# leto_ppm.net
KiCad netlist of a schematic drawn in EAGLE
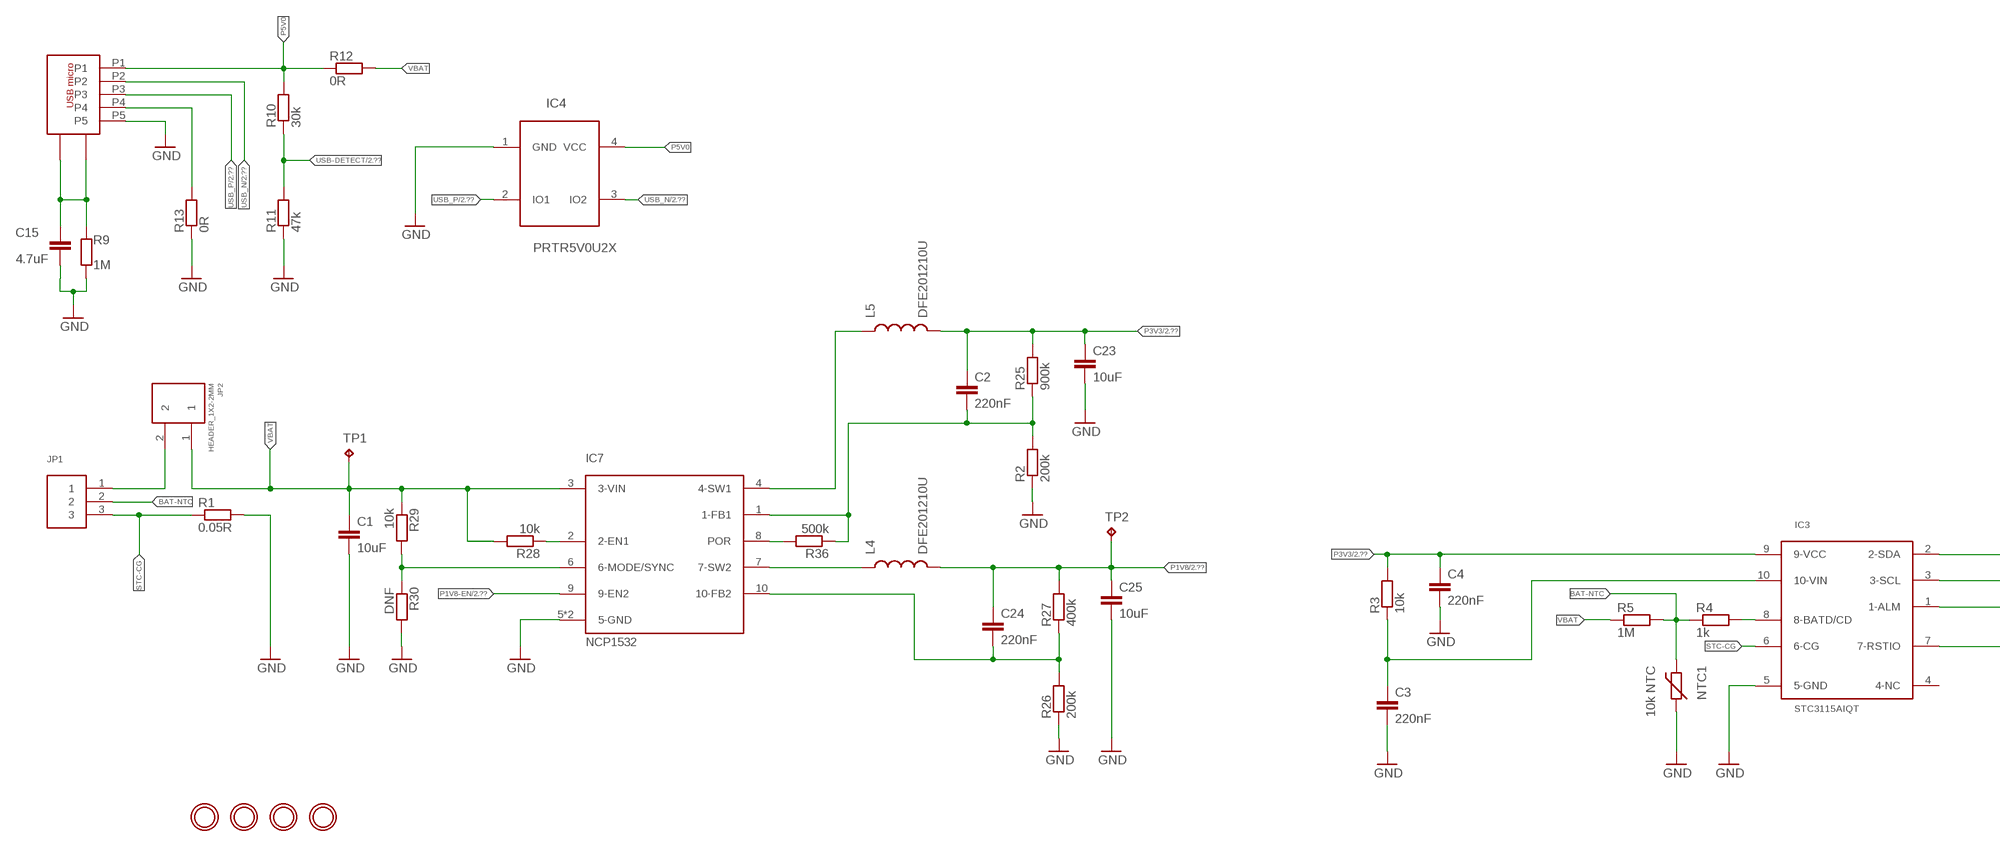
[diagram p0: schematic, sheet 1, part 1 of 2]
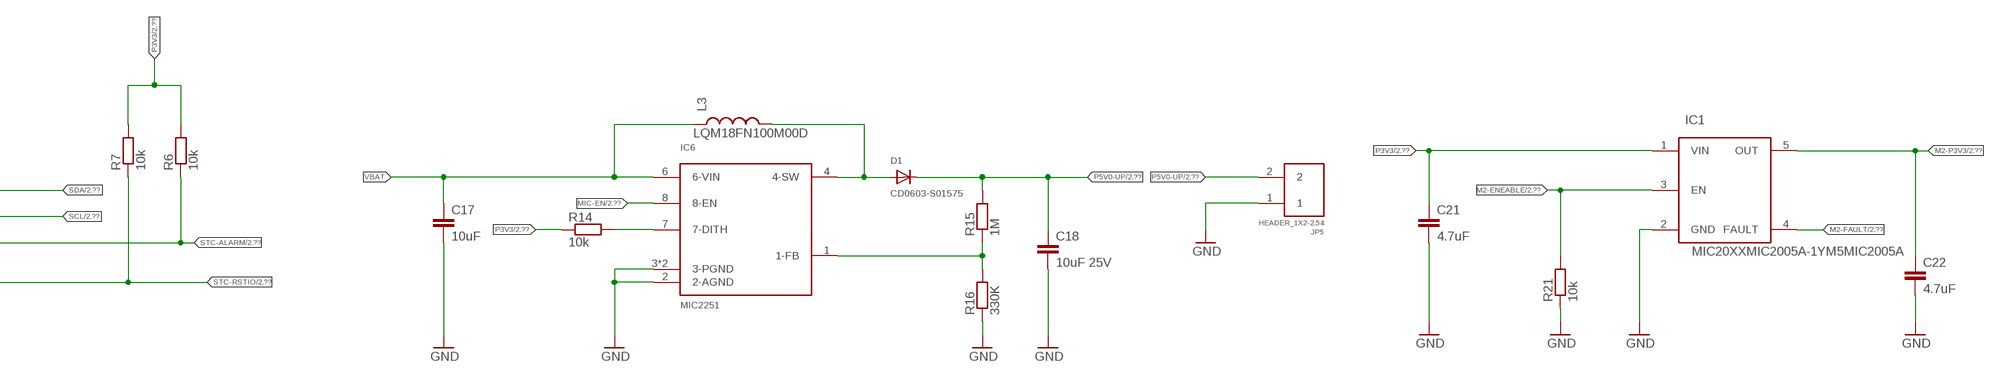
[diagram p1: schematic, sheet 1, part 2 of 2]
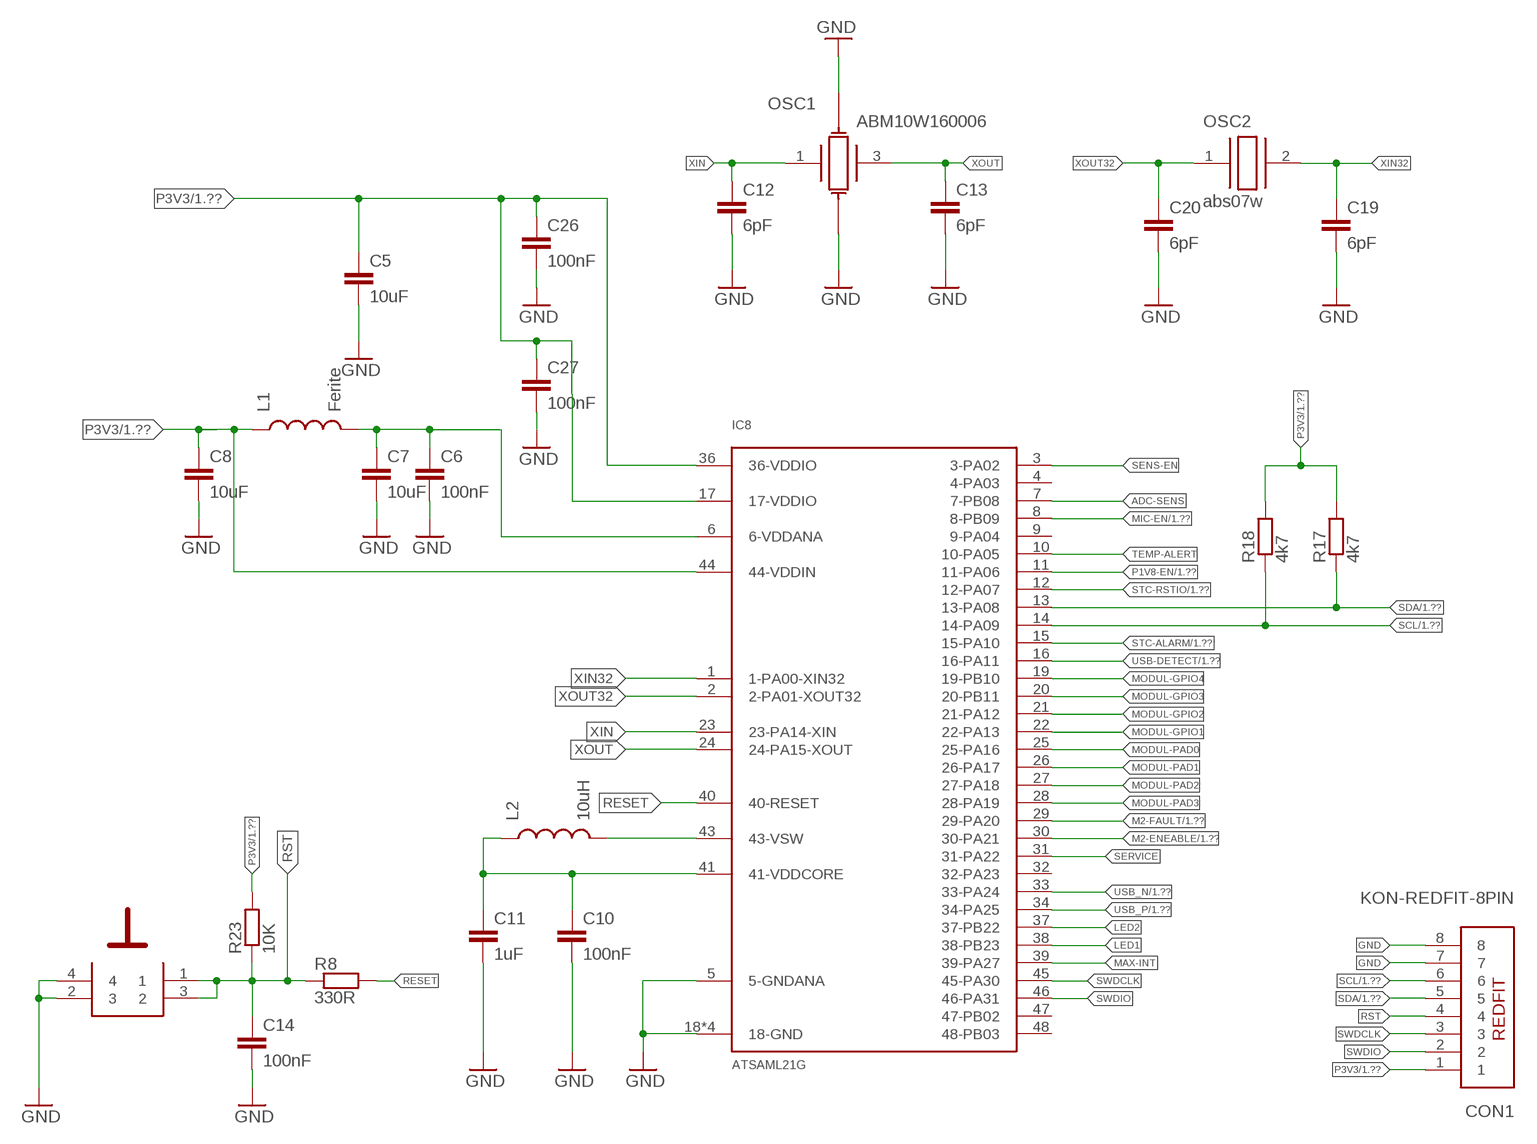
[diagram p2: schematic, sheet 2, part 1 of 2]
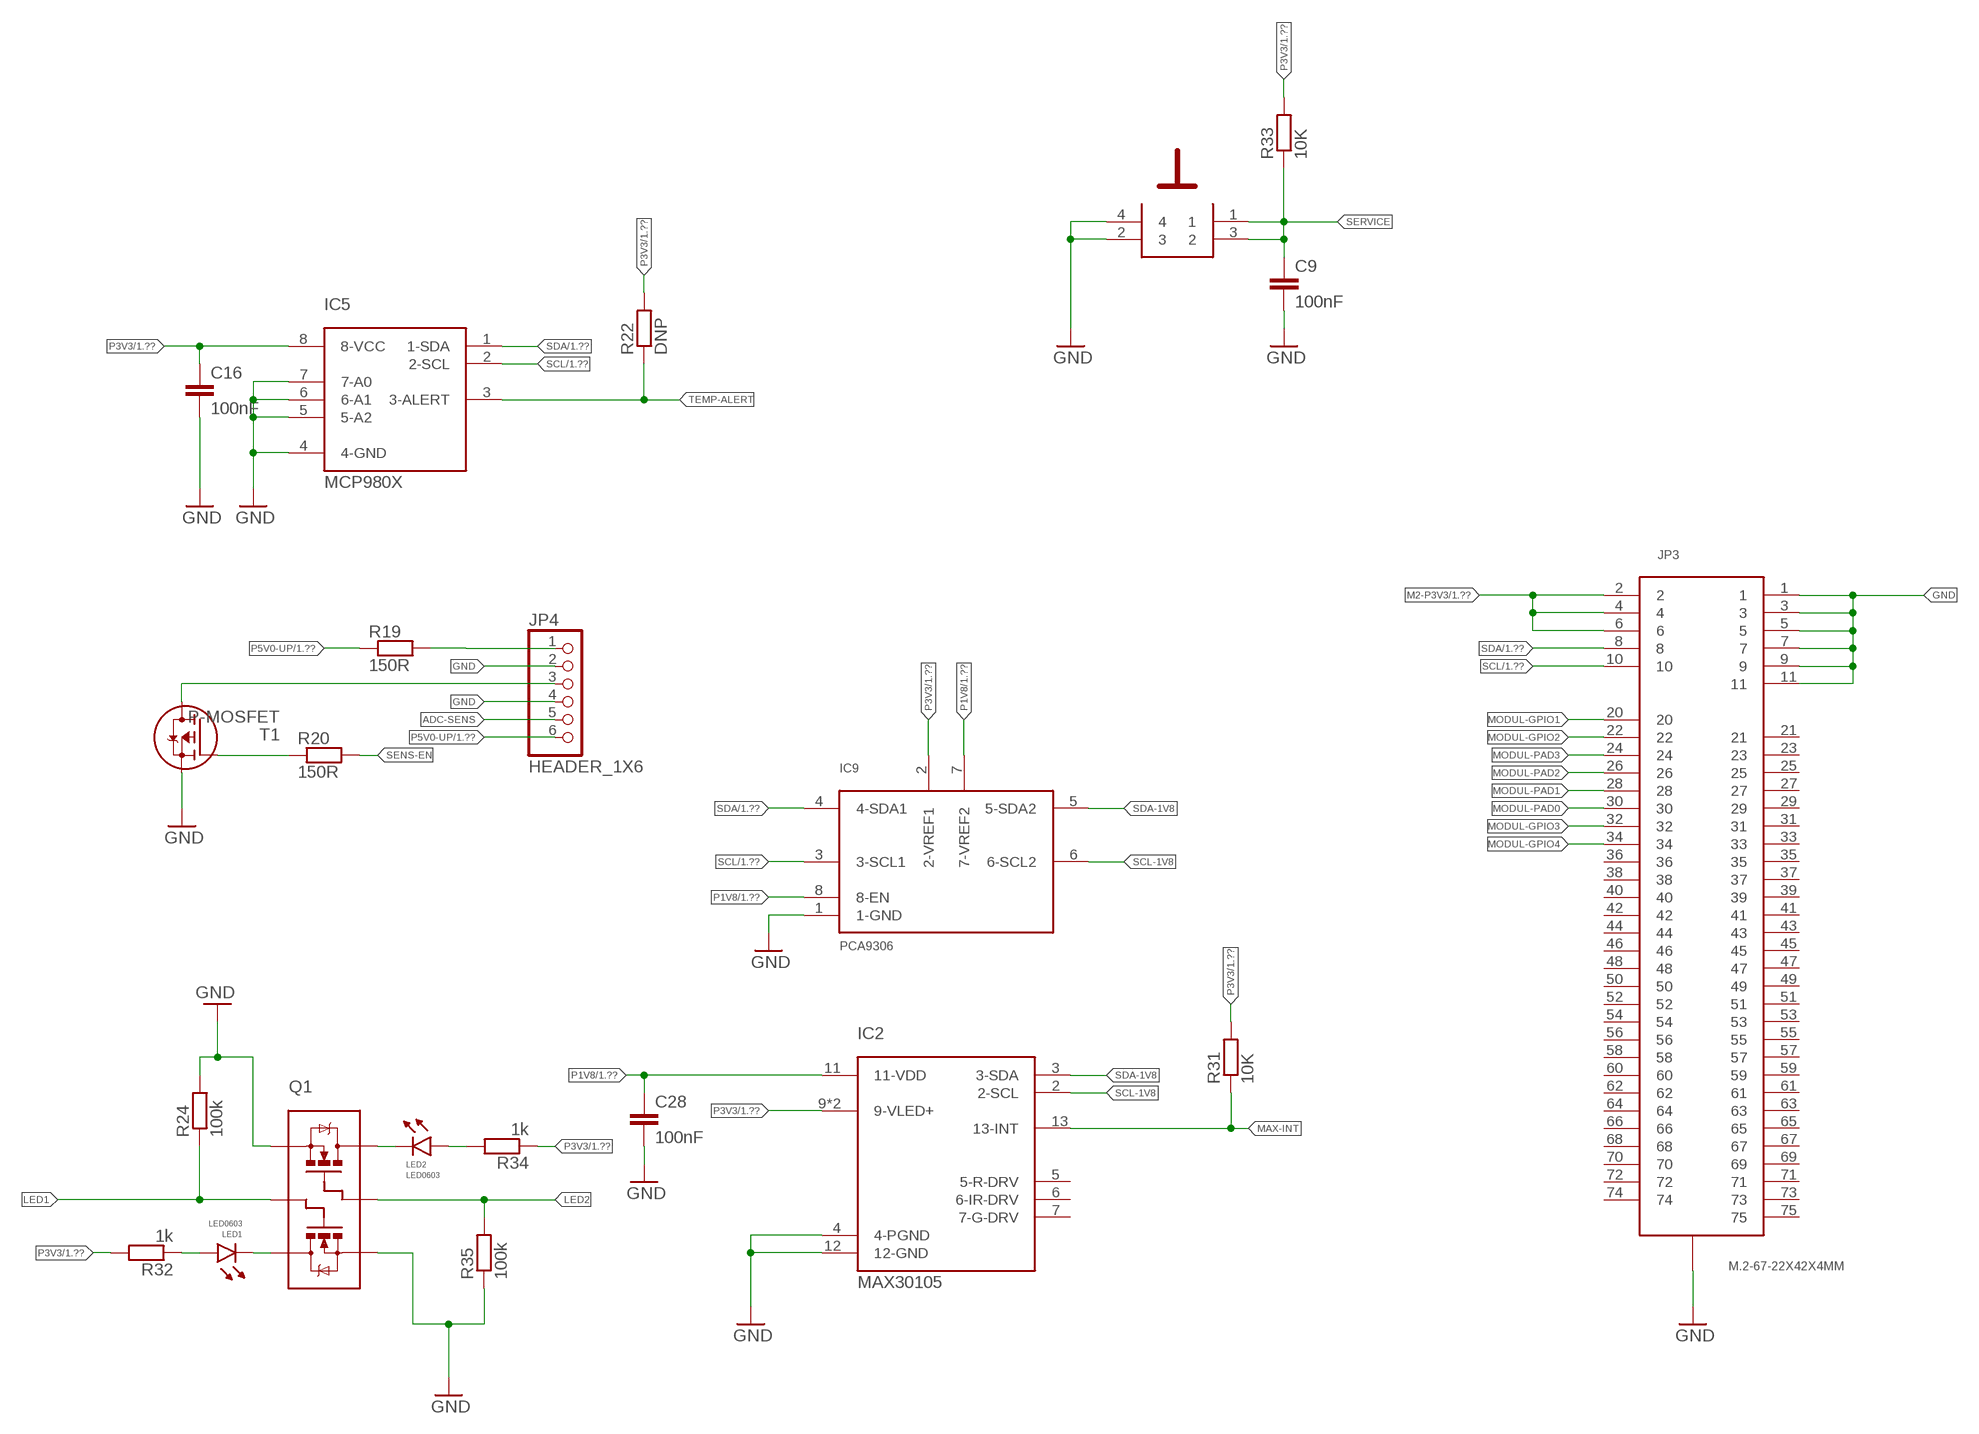
[diagram p3: schematic, sheet 2, part 2 of 2]

(export (version "E")
  (design (tool "Eeschema 10.0.6"))
  (components
    (comp (ref "C1")
      (value "10uF")
      (footprint "eagle-import:C0603")
      (libsource (lib "eagle-import") (part "C-EUC0603"))
    )
    (comp (ref "C2")
      (value "220nF")
      (footprint "eagle-import:C0402-SMALL")
      (libsource (lib "eagle-import") (part "C-EUC0402-SMALL"))
    )
    (comp (ref "C3")
      (value "220nF")
      (footprint "eagle-import:C0402-SMALL")
      (libsource (lib "eagle-import") (part "C-EUC0402-SMALL"))
    )
    (comp (ref "C4")
      (value "220nF")
      (footprint "eagle-import:C0402-SMALL")
      (libsource (lib "eagle-import") (part "C-EUC0402-SMALL"))
    )
    (comp (ref "C15")
      (value "4.7uF")
      (footprint "eagle-import:C0402-SMALL")
      (libsource (lib "eagle-import") (part "C-EUC0402-SMALL"))
    )
    (comp (ref "C17")
      (value "10uF")
      (footprint "eagle-import:C0603")
      (libsource (lib "eagle-import") (part "C-EUC0603"))
    )
    (comp (ref "C18")
      (value "10uF 25V")
      (footprint "eagle-import:C0603")
      (libsource (lib "eagle-import") (part "C-EUC0603"))
    )
    (comp (ref "C21")
      (value "4.7uF")
      (footprint "eagle-import:C0402-SMALL")
      (libsource (lib "eagle-import") (part "C-EUC0402-SMALL"))
    )
    (comp (ref "C22")
      (value "4.7uF")
      (footprint "eagle-import:C0402-SMALL")
      (libsource (lib "eagle-import") (part "C-EUC0402-SMALL"))
    )
    (comp (ref "C23")
      (value "10uF")
      (footprint "eagle-import:C0603")
      (libsource (lib "eagle-import") (part "C-EUC0603"))
    )
    (comp (ref "C24")
      (value "220nF")
      (footprint "eagle-import:C0402-SMALL")
      (libsource (lib "eagle-import") (part "C-EUC0402-SMALL"))
    )
    (comp (ref "C25")
      (value "10uF")
      (footprint "eagle-import:C0603")
      (libsource (lib "eagle-import") (part "C-EUC0603"))
    )
    (comp (ref "D1")
      (value "CD0603-S01575")
      (footprint "eagle-import:0603-DIODE")
      (libsource (lib "eagle-import") (part "DIODE"))
    )
    (comp (ref "IC1")
      (value "MIC20XXMIC2005A-1YM5MIC2005A")
      (footprint "eagle-import:SOT23-5")
      (libsource (lib "eagle-import") (part "MIC20XXMIC2005AMIC2005A-1YM5"))
    )
    (comp (ref "IC3")
      (value "STC3115AIQT")
      (footprint "eagle-import:DFN10_2X3MM")
      (libsource (lib "eagle-import") (part "STC3115AIQT"))
    )
    (comp (ref "IC4")
      (value "PRTR5V0U2X")
      (footprint "eagle-import:SOT143")
      (libsource (lib "eagle-import") (part "PRTR5V0U2X"))
    )
    (comp (ref "IC6")
      (value "MIC2251")
      (footprint "eagle-import:MLF-8-2X2")
      (libsource (lib "eagle-import") (part "MIC2251"))
    )
    (comp (ref "IC7")
      (value "NCP1532")
      (footprint "eagle-import:UDNF10-3X3")
      (libsource (lib "eagle-import") (part "NCP1532"))
    )
    (comp (ref "JP1")
      (value "HEADER_1X32.54MM")
      (footprint "eagle-import:1X3-2.54MM")
      (libsource (lib "eagle-import") (part "HEADER_1X32.54MM"))
    )
    (comp (ref "JP2")
      (value "HEADER_1X2-2MM")
      (footprint "eagle-import:1X2_2MM")
      (libsource (lib "eagle-import") (part "HEADER_1X2-2MM"))
    )
    (comp (ref "JP5")
      (value "HEADER_1X2-2.54")
      (footprint "eagle-import:1X2-2.54MM")
      (libsource (lib "eagle-import") (part "HEADER_1X2-2.54"))
    )
    (comp (ref "L3")
      (value "LQM18FN100M00D")
      (footprint "eagle-import:0603")
      (libsource (lib "eagle-import") (part "INDUCTOR0603"))
    )
    (comp (ref "L4")
      (value "DFE201210U")
      (footprint "eagle-import:0805")
      (libsource (lib "eagle-import") (part "INDUCTOR0805"))
    )
    (comp (ref "L5")
      (value "DFE201210U")
      (footprint "eagle-import:0805")
      (libsource (lib "eagle-import") (part "INDUCTOR0805"))
    )
    (comp (ref "MD1")
      (value "MOUNTINGHOLE2.5")
      (footprint "eagle-import:MOUNTINGHOLE_2.5_PLATED")
      (libsource (lib "eagle-import") (part "MOUNTINGHOLE2.5"))
    )
    (comp (ref "MD2")
      (value "MOUNTINGHOLE2.5")
      (footprint "eagle-import:MOUNTINGHOLE_2.5_PLATED")
      (libsource (lib "eagle-import") (part "MOUNTINGHOLE2.5"))
    )
    (comp (ref "MD3")
      (value "MOUNTINGHOLE2.5")
      (footprint "eagle-import:MOUNTINGHOLE_2.5_PLATED")
      (libsource (lib "eagle-import") (part "MOUNTINGHOLE2.5"))
    )
    (comp (ref "MD4")
      (value "MOUNTINGHOLE2.5")
      (footprint "eagle-import:MOUNTINGHOLE_2.5_PLATED")
      (libsource (lib "eagle-import") (part "MOUNTINGHOLE2.5"))
    )
    (comp (ref "NTC1")
      (value "10k NTC")
      (footprint "eagle-import:C0402-SMALL")
      (libsource (lib "eagle-import") (part "RESISTOR-NTC0402"))
    )
    (comp (ref "R1")
      (value "0.05R")
      (footprint "eagle-import:0603-RES")
      (libsource (lib "eagle-import") (part "RESISTOR0603-RES"))
    )
    (comp (ref "R2")
      (value "200k")
      (footprint "eagle-import:C0402-SMALL")
      (libsource (lib "eagle-import") (part "RESISTORC0402-SMALL"))
    )
    (comp (ref "R3")
      (value "10k")
      (footprint "eagle-import:C0402-SMALL")
      (libsource (lib "eagle-import") (part "RESISTORC0402-SMALL"))
    )
    (comp (ref "R4")
      (value "1k")
      (footprint "eagle-import:C0402-SMALL")
      (libsource (lib "eagle-import") (part "RESISTORC0402-SMALL"))
    )
    (comp (ref "R5")
      (value "1M")
      (footprint "eagle-import:C0402-SMALL")
      (libsource (lib "eagle-import") (part "RESISTORC0402-SMALL"))
    )
    (comp (ref "R6")
      (value "10k")
      (footprint "eagle-import:C0402-SMALL")
      (libsource (lib "eagle-import") (part "RESISTORC0402-SMALL"))
    )
    (comp (ref "R7")
      (value "10k")
      (footprint "eagle-import:C0402-SMALL")
      (libsource (lib "eagle-import") (part "RESISTORC0402-SMALL"))
    )
    (comp (ref "R9")
      (value "1M")
      (footprint "eagle-import:C0402-SMALL")
      (libsource (lib "eagle-import") (part "RESISTORC0402-SMALL"))
    )
    (comp (ref "R10")
      (value "30k")
      (footprint "eagle-import:C0402-SMALL")
      (libsource (lib "eagle-import") (part "RESISTORC0402-SMALL"))
    )
    (comp (ref "R11")
      (value "47k")
      (footprint "eagle-import:C0402-SMALL")
      (libsource (lib "eagle-import") (part "RESISTORC0402-SMALL"))
    )
    (comp (ref "R12")
      (value "0R")
      (footprint "eagle-import:C0402-SMALL")
      (libsource (lib "eagle-import") (part "RESISTORC0402-SMALL"))
    )
    (comp (ref "R13")
      (value "0R")
      (footprint "eagle-import:C0402-SMALL")
      (libsource (lib "eagle-import") (part "RESISTORC0402-SMALL"))
    )
    (comp (ref "R14")
      (value "10k")
      (footprint "eagle-import:C0402-SMALL")
      (libsource (lib "eagle-import") (part "RESISTORC0402-SMALL"))
    )
    (comp (ref "R15")
      (value "1M")
      (footprint "eagle-import:C0402-SMALL")
      (libsource (lib "eagle-import") (part "RESISTORC0402-SMALL"))
    )
    (comp (ref "R16")
      (value "330K")
      (footprint "eagle-import:C0402-SMALL")
      (libsource (lib "eagle-import") (part "RESISTORC0402-SMALL"))
    )
    (comp (ref "R21")
      (value "10k")
      (footprint "eagle-import:C0402-SMALL")
      (libsource (lib "eagle-import") (part "RESISTORC0402-SMALL"))
    )
    (comp (ref "R25")
      (value "900k")
      (footprint "eagle-import:C0402-SMALL")
      (libsource (lib "eagle-import") (part "RESISTORC0402-SMALL"))
    )
    (comp (ref "R26")
      (value "200k")
      (footprint "eagle-import:C0402-SMALL")
      (libsource (lib "eagle-import") (part "RESISTORC0402-SMALL"))
    )
    (comp (ref "R27")
      (value "400k")
      (footprint "eagle-import:C0402-SMALL")
      (libsource (lib "eagle-import") (part "RESISTORC0402-SMALL"))
    )
    (comp (ref "R28")
      (value "10k")
      (footprint "eagle-import:C0402-SMALL")
      (libsource (lib "eagle-import") (part "RESISTORC0402-SMALL"))
    )
    (comp (ref "R29")
      (value "10k")
      (footprint "eagle-import:C0402-SMALL")
      (libsource (lib "eagle-import") (part "RESISTORC0402-SMALL"))
    )
    (comp (ref "R30")
      (value "DNF")
      (footprint "eagle-import:C0402-SMALL")
      (libsource (lib "eagle-import") (part "RESISTORC0402-SMALL"))
    )
    (comp (ref "R36")
      (value "500k")
      (footprint "eagle-import:C0402-SMALL")
      (libsource (lib "eagle-import") (part "RESISTORC0402-SMALL"))
    )
    (comp (ref "TP1")
      (value "TPTP20R")
      (footprint "eagle-import:TP20R")
      (libsource (lib "eagle-import") (part "TPTP20R"))
    )
    (comp (ref "TP2")
      (value "TPTP11R")
      (footprint "eagle-import:TP11R")
      (libsource (lib "eagle-import") (part "testpad_385_TPTP11R"))
    )
    (comp (ref "USB1")
      (value "USB3140-30")
      (footprint "eagle-import:USB3140-30-0230")
      (libsource (lib "eagle-import") (part "USB3140-30"))
    )
    (comp (ref "C5")
      (value "10uF")
      (footprint "eagle-import:C0603")
      (libsource (lib "eagle-import") (part "C-EUC0603"))
    )
    (comp (ref "C6")
      (value "100nF")
      (footprint "eagle-import:C0402-SMALL")
      (libsource (lib "eagle-import") (part "C-EUC0402-SMALL"))
    )
    (comp (ref "C7")
      (value "10uF")
      (footprint "eagle-import:C0603")
      (libsource (lib "eagle-import") (part "C-EUC0603"))
    )
    (comp (ref "C8")
      (value "10uF")
      (footprint "eagle-import:C0603")
      (libsource (lib "eagle-import") (part "C-EUC0603"))
    )
    (comp (ref "C9")
      (value "100nF")
      (footprint "eagle-import:C0402-SMALL")
      (libsource (lib "eagle-import") (part "C-EUC0402-SMALL"))
    )
    (comp (ref "C10")
      (value "100nF")
      (footprint "eagle-import:C0402-SMALL")
      (libsource (lib "eagle-import") (part "C-EUC0402-SMALL"))
    )
    (comp (ref "C11")
      (value "1uF")
      (footprint "eagle-import:C0402-SMALL")
      (libsource (lib "eagle-import") (part "C-EUC0402-SMALL"))
    )
    (comp (ref "C12")
      (value "6pF")
      (footprint "eagle-import:C0402-SMALL")
      (libsource (lib "eagle-import") (part "C-EUC0402-SMALL"))
    )
    (comp (ref "C13")
      (value "6pF")
      (footprint "eagle-import:C0402-SMALL")
      (libsource (lib "eagle-import") (part "C-EUC0402-SMALL"))
    )
    (comp (ref "C14")
      (value "100nF")
      (footprint "eagle-import:C0402-SMALL")
      (libsource (lib "eagle-import") (part "C-EUC0402-SMALL"))
    )
    (comp (ref "C16")
      (value "100nF")
      (footprint "eagle-import:C0402-SMALL")
      (libsource (lib "eagle-import") (part "C-EUC0402-SMALL"))
    )
    (comp (ref "C19")
      (value "6pF")
      (footprint "eagle-import:C0402-SMALL")
      (libsource (lib "eagle-import") (part "C-EUC0402-SMALL"))
    )
    (comp (ref "C20")
      (value "6pF")
      (footprint "eagle-import:C0402-SMALL")
      (libsource (lib "eagle-import") (part "C-EUC0402-SMALL"))
    )
    (comp (ref "C26")
      (value "100nF")
      (footprint "eagle-import:C0402-SMALL")
      (libsource (lib "eagle-import") (part "C-EUC0402-SMALL"))
    )
    (comp (ref "C27")
      (value "100nF")
      (footprint "eagle-import:C0402-SMALL")
      (libsource (lib "eagle-import") (part "C-EUC0402-SMALL"))
    )
    (comp (ref "C28")
      (value "100nF")
      (footprint "eagle-import:C0402-SMALL")
      (libsource (lib "eagle-import") (part "C-EUC0402-SMALL"))
    )
    (comp (ref "CON1")
      (value "KON-REDFIT-8PIN")
      (footprint "eagle-import:KON-REDFIT-8PIN")
      (libsource (lib "eagle-import") (part "KON-REDFIT-8PIN"))
    )
    (comp (ref "IC2")
      (value "MAX30105")
      (footprint "eagle-import:14-OESIP")
      (libsource (lib "eagle-import") (part "MAX30105"))
    )
    (comp (ref "IC5")
      (value "MCP980X")
      (footprint "eagle-import:DNF82X3MM")
      (libsource (lib "eagle-import") (part "MCP980X"))
    )
    (comp (ref "IC8")
      (value "ATSAML21G")
      (footprint "eagle-import:QFN48")
      (libsource (lib "eagle-import") (part "ATSAML21G"))
    )
    (comp (ref "IC9")
      (value "PCA9306")
      (footprint "eagle-import:SO8")
      (libsource (lib "eagle-import") (part "PCA9306"))
    )
    (comp (ref "JP3")
      (value "M.2-67-22X42X4MM")
      (footprint "eagle-import:M2-67POS-0.5MM")
      (libsource (lib "eagle-import") (part "M.2-67-22X42X4MM"))
    )
    (comp (ref "JP4")
      (value "HEADER_1X6")
      (footprint "eagle-import:1X6_2.54")
      (libsource (lib "eagle-import") (part "HEADER_1X6"))
    )
    (comp (ref "L1")
      (value "Ferite")
      (footprint "eagle-import:0603")
      (libsource (lib "eagle-import") (part "INDUCTOR0603"))
    )
    (comp (ref "L2")
      (value "10uH")
      (footprint "eagle-import:0603")
      (libsource (lib "eagle-import") (part "INDUCTOR0603"))
    )
    (comp (ref "LED1")
      (value "LED0603")
      (footprint "eagle-import:0603-DIODE")
      (libsource (lib "eagle-import") (part "LED0603"))
    )
    (comp (ref "LED2")
      (value "LED0603")
      (footprint "eagle-import:0603-DIODE")
      (libsource (lib "eagle-import") (part "LED0603"))
    )
    (comp (ref "OSC1")
      (value "ABM10W160006")
      (footprint "eagle-import:ABM10W")
      (libsource (lib "eagle-import") (part "CRYSTAL-GNDABM10W"))
    )
    (comp (ref "OSC2")
      (value "abs07w")
      (footprint "eagle-import:ABS07W")
      (libsource (lib "eagle-import") (part "CRYSTAL"))
    )
    (comp (ref "Q1")
      (value "MOSFET-N-X2-SOT363")
      (footprint "eagle-import:SOT363")
      (libsource (lib "eagle-import") (part "MOSFET-N-X2-SOT363"))
    )
    (comp (ref "R8")
      (value "330R")
      (footprint "eagle-import:C0402-SMALL")
      (libsource (lib "eagle-import") (part "RESISTORC0402-SMALL"))
    )
    (comp (ref "R17")
      (value "4k7")
      (footprint "eagle-import:C0402-SMALL")
      (libsource (lib "eagle-import") (part "RESISTORC0402-SMALL"))
    )
    (comp (ref "R18")
      (value "4k7")
      (footprint "eagle-import:C0402-SMALL")
      (libsource (lib "eagle-import") (part "RESISTORC0402-SMALL"))
    )
    (comp (ref "R19")
      (value "150R")
      (footprint "eagle-import:C0402-SMALL")
      (libsource (lib "eagle-import") (part "RESISTORC0402-SMALL"))
    )
    (comp (ref "R20")
      (value "150R")
      (footprint "eagle-import:C0402-SMALL")
      (libsource (lib "eagle-import") (part "RESISTORC0402-SMALL"))
    )
    (comp (ref "R22")
      (value "DNP")
      (footprint "eagle-import:C0402-SMALL")
      (libsource (lib "eagle-import") (part "RESISTORC0402-SMALL"))
    )
    (comp (ref "R23")
      (value "10K")
      (footprint "eagle-import:C0402-SMALL")
      (libsource (lib "eagle-import") (part "RESISTORC0402-SMALL"))
    )
    (comp (ref "R24")
      (value "100k")
      (footprint "eagle-import:C0402-SMALL")
      (libsource (lib "eagle-import") (part "RESISTORC0402-SMALL"))
    )
    (comp (ref "R31")
      (value "10K")
      (footprint "eagle-import:C0402-SMALL")
      (libsource (lib "eagle-import") (part "RESISTORC0402-SMALL"))
    )
    (comp (ref "R32")
      (value "1k")
      (footprint "eagle-import:C0402-SMALL")
      (libsource (lib "eagle-import") (part "RESISTORC0402-SMALL"))
    )
    (comp (ref "R33")
      (value "10K")
      (footprint "eagle-import:C0402-SMALL")
      (libsource (lib "eagle-import") (part "RESISTORC0402-SMALL"))
    )
    (comp (ref "R34")
      (value "1k")
      (footprint "eagle-import:C0402-SMALL")
      (libsource (lib "eagle-import") (part "RESISTORC0402-SMALL"))
    )
    (comp (ref "R35")
      (value "100k")
      (footprint "eagle-import:C0402-SMALL")
      (libsource (lib "eagle-import") (part "RESISTORC0402-SMALL"))
    )
    (comp (ref "RESET")
      (value "TACTB")
      (footprint "eagle-import:TACTB-64K-F")
      (libsource (lib "eagle-import") (part "TACTB"))
    )
    (comp (ref "SERVICE")
      (value "TACTB")
      (footprint "eagle-import:TACTB-64K-F")
      (libsource (lib "eagle-import") (part "TACTB"))
    )
    (comp (ref "T1")
      (value "P-MOSFET")
      (footprint "eagle-import:SOT23-R")
      (libsource (lib "eagle-import") (part "P-MOSFET"))
    )
  )
  (nets
    (net (code "1") (name "ADC-SENS") (class "Default")
      (node (ref "IC8") (pin "7") (pinfunction "7-PB08_7") (pintype "bidirectional"))
      (node (ref "JP4") (pin "5") (pinfunction "5_5") (pintype "passive"))
    )
    (net (code "2") (name "BAT-NTC") (class "Default")
      (node (ref "JP1") (pin "2") (pinfunction "2_2") (pintype "bidirectional"))
      (node (ref "NTC1") (pin "1") (pinfunction "1_1") (pintype "passive"))
      (node (ref "R4") (pin "1") (pinfunction "1_1") (pintype "passive"))
      (node (ref "R5") (pin "2") (pinfunction "2_2") (pintype "passive"))
    )
    (net (code "3") (name "GND") (class "Default")
      (node (ref "C1") (pin "2") (pinfunction "2_2") (pintype "passive"))
      (node (ref "C10") (pin "2") (pinfunction "2_2") (pintype "passive"))
      (node (ref "C11") (pin "2") (pinfunction "2_2") (pintype "passive"))
      (node (ref "C12") (pin "2") (pinfunction "2_2") (pintype "passive"))
      (node (ref "C13") (pin "2") (pinfunction "2_2") (pintype "passive"))
      (node (ref "C14") (pin "2") (pinfunction "2_2") (pintype "passive"))
      (node (ref "C15") (pin "2") (pinfunction "2_2") (pintype "passive"))
      (node (ref "C16") (pin "2") (pinfunction "2_2") (pintype "passive"))
      (node (ref "C17") (pin "2") (pinfunction "2_2") (pintype "passive"))
      (node (ref "C18") (pin "2") (pinfunction "2_2") (pintype "passive"))
      (node (ref "C19") (pin "2") (pinfunction "2_2") (pintype "passive"))
      (node (ref "C20") (pin "2") (pinfunction "2_2") (pintype "passive"))
      (node (ref "C21") (pin "2") (pinfunction "2_2") (pintype "passive"))
      (node (ref "C22") (pin "2") (pinfunction "2_2") (pintype "passive"))
      (node (ref "C23") (pin "2") (pinfunction "2_2") (pintype "passive"))
      (node (ref "C25") (pin "2") (pinfunction "2_2") (pintype "passive"))
      (node (ref "C26") (pin "2") (pinfunction "2_2") (pintype "passive"))
      (node (ref "C27") (pin "2") (pinfunction "2_2") (pintype "passive"))
      (node (ref "C28") (pin "2") (pinfunction "2_2") (pintype "passive"))
      (node (ref "C3") (pin "2") (pinfunction "2_2") (pintype "passive"))
      (node (ref "C4") (pin "2") (pinfunction "2_2") (pintype "passive"))
      (node (ref "C5") (pin "2") (pinfunction "2_2") (pintype "passive"))
      (node (ref "C6") (pin "2") (pinfunction "2_2") (pintype "passive"))
      (node (ref "C7") (pin "2") (pinfunction "2_2") (pintype "passive"))
      (node (ref "C8") (pin "2") (pinfunction "2_2") (pintype "passive"))
      (node (ref "C9") (pin "2") (pinfunction "2_2") (pintype "passive"))
      (node (ref "CON1") (pin "7") (pinfunction "7_7") (pintype "bidirectional"))
      (node (ref "CON1") (pin "8") (pinfunction "8_8") (pintype "bidirectional"))
      (node (ref "IC1") (pin "2") (pinfunction "GND_2") (pintype "bidirectional"))
      (node (ref "IC2") (pin "12") (pinfunction "12-GND_12") (pintype "bidirectional"))
      (node (ref "IC2") (pin "4") (pinfunction "4-PGND_4") (pintype "bidirectional"))
      (node (ref "IC3") (pin "5") (pinfunction "5-GND_5") (pintype "bidirectional"))
      (node (ref "IC4") (pin "1") (pinfunction "GND_1") (pintype "bidirectional"))
      (node (ref "IC5") (pin "4") (pinfunction "4-GND_4") (pintype "bidirectional"))
      (node (ref "IC5") (pin "5") (pinfunction "5-A2_5") (pintype "bidirectional"))
      (node (ref "IC5") (pin "6") (pinfunction "6-A1_6") (pintype "bidirectional"))
      (node (ref "IC5") (pin "7") (pinfunction "7-A0_7") (pintype "bidirectional"))
      (node (ref "IC6") (pin "2") (pinfunction "2-AGND_2") (pintype "bidirectional"))
      (node (ref "IC6") (pin "3") (pinfunction "3-PGND_3") (pintype "bidirectional"))
      (node (ref "IC6") (pin "EP") (pinfunction "3-PGND_EP") (pintype "bidirectional"))
      (node (ref "IC7") (pin "5") (pinfunction "5-GND_5") (pintype "bidirectional"))
      (node (ref "IC7") (pin "P$11") (pinfunction "5-GND_P$11") (pintype "bidirectional"))
      (node (ref "IC8") (pin "18") (pinfunction "18-GND_18") (pintype "bidirectional"))
      (node (ref "IC8") (pin "35") (pinfunction "18-GND_35") (pintype "bidirectional"))
      (node (ref "IC8") (pin "42") (pinfunction "18-GND_42") (pintype "bidirectional"))
      (node (ref "IC8") (pin "5") (pinfunction "5-GNDANA_5") (pintype "bidirectional"))
      (node (ref "IC8") (pin "EP") (pinfunction "18-GND_EP") (pintype "bidirectional"))
      (node (ref "IC9") (pin "1") (pinfunction "1-GND_1") (pintype "bidirectional"))
      (node (ref "JP3") (pin "1") (pinfunction "1_1") (pintype "bidirectional"))
      (node (ref "JP3") (pin "11") (pinfunction "11_11") (pintype "bidirectional"))
      (node (ref "JP3") (pin "3") (pinfunction "3_3") (pintype "bidirectional"))
      (node (ref "JP3") (pin "5") (pinfunction "5_5") (pintype "bidirectional"))
      (node (ref "JP3") (pin "7") (pinfunction "7_7") (pintype "bidirectional"))
      (node (ref "JP3") (pin "9") (pinfunction "9_9") (pintype "bidirectional"))
      (node (ref "JP3") (pin "GND_SCRW") (pinfunction "SCREW_GND_SCRW") (pintype "bidirectional"))
      (node (ref "JP4") (pin "2") (pinfunction "2_2") (pintype "passive"))
      (node (ref "JP4") (pin "4") (pinfunction "4_4") (pintype "passive"))
      (node (ref "JP5") (pin "1") (pinfunction "1_1") (pintype "bidirectional"))
      (node (ref "NTC1") (pin "2") (pinfunction "2_2") (pintype "passive"))
      (node (ref "OSC1") (pin "2") (pinfunction "1GND_2") (pintype "bidirectional"))
      (node (ref "OSC1") (pin "4") (pinfunction "GND_4") (pintype "bidirectional"))
      (node (ref "Q1") (pin "1") (pinfunction "S2_1") (pintype "bidirectional"))
      (node (ref "Q1") (pin "4") (pinfunction "S1_4") (pintype "bidirectional"))
      (node (ref "R1") (pin "2") (pinfunction "2_2") (pintype "passive"))
      (node (ref "R11") (pin "1") (pinfunction "1_1") (pintype "passive"))
      (node (ref "R13") (pin "1") (pinfunction "1_1") (pintype "passive"))
      (node (ref "R16") (pin "1") (pinfunction "1_1") (pintype "passive"))
      (node (ref "R2") (pin "1") (pinfunction "1_1") (pintype "passive"))
      (node (ref "R21") (pin "1") (pinfunction "1_1") (pintype "passive"))
      (node (ref "R24") (pin "2") (pinfunction "2_2") (pintype "passive"))
      (node (ref "R26") (pin "1") (pinfunction "1_1") (pintype "passive"))
      (node (ref "R30") (pin "2") (pinfunction "2_2") (pintype "passive"))
      (node (ref "R35") (pin "1") (pinfunction "1_1") (pintype "passive"))
      (node (ref "R9") (pin "1") (pinfunction "1_1") (pintype "passive"))
      (node (ref "RESET") (pin "2") (pinfunction "3_2") (pintype "bidirectional"))
      (node (ref "RESET") (pin "4") (pinfunction "4_4") (pintype "bidirectional"))
      (node (ref "SERVICE") (pin "2") (pinfunction "3_2") (pintype "bidirectional"))
      (node (ref "SERVICE") (pin "4") (pinfunction "4_4") (pintype "bidirectional"))
      (node (ref "T1") (pin "2") (pinfunction "S_2") (pintype "passive"))
      (node (ref "USB1") (pin "P5") (pinfunction "P5_P5") (pintype "bidirectional"))
    )
    (net (code "4") (name "LED1") (class "Default")
      (node (ref "IC8") (pin "38") (pinfunction "38-PB23_38") (pintype "bidirectional"))
      (node (ref "Q1") (pin "2") (pinfunction "G2_2") (pintype "bidirectional"))
      (node (ref "R24") (pin "1") (pinfunction "1_1") (pintype "passive"))
    )
    (net (code "5") (name "LED2") (class "Default")
      (node (ref "IC8") (pin "37") (pinfunction "37-PB22_37") (pintype "bidirectional"))
      (node (ref "Q1") (pin "5") (pinfunction "G1_5") (pintype "bidirectional"))
      (node (ref "R35") (pin "2") (pinfunction "2_2") (pintype "passive"))
    )
    (net (code "6") (name "M2-ENEABLE") (class "Default")
      (node (ref "IC1") (pin "3") (pinfunction "EN_3") (pintype "bidirectional"))
      (node (ref "IC8") (pin "30") (pinfunction "30-PA21_30") (pintype "bidirectional"))
      (node (ref "R21") (pin "2") (pinfunction "2_2") (pintype "passive"))
    )
    (net (code "7") (name "M2-FAULT") (class "Default")
      (node (ref "IC1") (pin "4") (pinfunction "FAULT_4") (pintype "bidirectional"))
      (node (ref "IC8") (pin "29") (pinfunction "29-PA20_29") (pintype "bidirectional"))
    )
    (net (code "8") (name "M2-P3V3") (class "Default")
      (node (ref "C22") (pin "1") (pinfunction "1_1") (pintype "passive"))
      (node (ref "IC1") (pin "5") (pinfunction "OUT_5") (pintype "bidirectional"))
      (node (ref "JP3") (pin "2") (pinfunction "2_2") (pintype "bidirectional"))
      (node (ref "JP3") (pin "4") (pinfunction "4_4") (pintype "bidirectional"))
      (node (ref "JP3") (pin "6") (pinfunction "6_6") (pintype "bidirectional"))
    )
    (net (code "9") (name "MAX-INT") (class "Default")
      (node (ref "IC2") (pin "13") (pinfunction "13-INT_13") (pintype "bidirectional"))
      (node (ref "IC8") (pin "39") (pinfunction "39-PA27_39") (pintype "bidirectional"))
      (node (ref "R31") (pin "1") (pinfunction "1_1") (pintype "passive"))
    )
    (net (code "10") (name "MIC-EN") (class "Default")
      (node (ref "IC6") (pin "8") (pinfunction "8-EN_8") (pintype "bidirectional"))
      (node (ref "IC8") (pin "8") (pinfunction "8-PB09_8") (pintype "bidirectional"))
    )
    (net (code "11") (name "MODUL-GPIO1") (class "Default")
      (node (ref "IC8") (pin "22") (pinfunction "22-PA13_22") (pintype "bidirectional"))
      (node (ref "JP3") (pin "20") (pinfunction "20_20") (pintype "bidirectional"))
    )
    (net (code "12") (name "MODUL-GPIO2") (class "Default")
      (node (ref "IC8") (pin "21") (pinfunction "21-PA12_21") (pintype "bidirectional"))
      (node (ref "JP3") (pin "22") (pinfunction "22_22") (pintype "bidirectional"))
    )
    (net (code "13") (name "MODUL-GPIO3") (class "Default")
      (node (ref "IC8") (pin "20") (pinfunction "20-PB11_20") (pintype "bidirectional"))
      (node (ref "JP3") (pin "32") (pinfunction "32_32") (pintype "bidirectional"))
    )
    (net (code "14") (name "MODUL-GPIO4") (class "Default")
      (node (ref "IC8") (pin "19") (pinfunction "19-PB10_19") (pintype "bidirectional"))
      (node (ref "JP3") (pin "34") (pinfunction "34_34") (pintype "bidirectional"))
    )
    (net (code "15") (name "MODUL-PAD0") (class "Default")
      (node (ref "IC8") (pin "25") (pinfunction "25-PA16_25") (pintype "bidirectional"))
      (node (ref "JP3") (pin "30") (pinfunction "30_30") (pintype "bidirectional"))
    )
    (net (code "16") (name "MODUL-PAD1") (class "Default")
      (node (ref "IC8") (pin "26") (pinfunction "26-PA17_26") (pintype "bidirectional"))
      (node (ref "JP3") (pin "28") (pinfunction "28_28") (pintype "bidirectional"))
    )
    (net (code "17") (name "MODUL-PAD2") (class "Default")
      (node (ref "IC8") (pin "27") (pinfunction "27-PA18_27") (pintype "bidirectional"))
      (node (ref "JP3") (pin "26") (pinfunction "26_26") (pintype "bidirectional"))
    )
    (net (code "18") (name "MODUL-PAD3") (class "Default")
      (node (ref "IC8") (pin "28") (pinfunction "28-PA19_28") (pintype "bidirectional"))
      (node (ref "JP3") (pin "24") (pinfunction "24_24") (pintype "bidirectional"))
    )
    (net (code "19") (name "Net-(C15-Pad1)") (class "Default")
      (node (ref "C15") (pin "1") (pinfunction "1_1") (pintype "passive"))
      (node (ref "R9") (pin "2") (pinfunction "2_2") (pintype "passive"))
      (node (ref "USB1") (pin "GND1") (pinfunction "GND1_GND1") (pintype "bidirectional"))
      (node (ref "USB1") (pin "GND2") (pinfunction "GND2_GND2") (pintype "bidirectional"))
    )
    (net (code "20") (name "Net-(IC3-8-BATD{slash}CD)") (class "Default")
      (node (ref "IC3") (pin "8") (pinfunction "8-BATD/CD_8") (pintype "bidirectional"))
      (node (ref "R4") (pin "2") (pinfunction "2_2") (pintype "passive"))
    )
    (net (code "21") (name "Net-(IC3-10-VIN)") (class "Default")
      (node (ref "C3") (pin "1") (pinfunction "1_1") (pintype "passive"))
      (node (ref "IC3") (pin "10") (pinfunction "10-VIN_10") (pintype "bidirectional"))
      (node (ref "R3") (pin "1") (pinfunction "1_1") (pintype "passive"))
    )
    (net (code "22") (name "Net-(IC6-1-FB)") (class "Default")
      (node (ref "IC6") (pin "1") (pinfunction "1-FB_1") (pintype "bidirectional"))
      (node (ref "R15") (pin "1") (pinfunction "1_1") (pintype "passive"))
      (node (ref "R16") (pin "2") (pinfunction "2_2") (pintype "passive"))
    )
    (net (code "23") (name "Net-(IC6-4-SW)") (class "Default")
      (node (ref "D1") (pin "A") (pinfunction "A_A") (pintype "passive"))
      (node (ref "IC6") (pin "4") (pinfunction "4-SW_4") (pintype "bidirectional"))
      (node (ref "L3") (pin "2") (pinfunction "2_2") (pintype "passive"))
    )
    (net (code "24") (name "Net-(IC6-7-DITH)") (class "Default")
      (node (ref "IC6") (pin "7") (pinfunction "7-DITH_7") (pintype "bidirectional"))
      (node (ref "R14") (pin "2") (pinfunction "2_2") (pintype "passive"))
    )
    (net (code "25") (name "Net-(IC7-1-FB1)") (class "Default")
      (node (ref "C2") (pin "2") (pinfunction "2_2") (pintype "passive"))
      (node (ref "IC7") (pin "1") (pinfunction "1-FB1_1") (pintype "bidirectional"))
      (node (ref "R2") (pin "2") (pinfunction "2_2") (pintype "passive"))
      (node (ref "R25") (pin "1") (pinfunction "1_1") (pintype "passive"))
      (node (ref "R36") (pin "1") (pinfunction "1_1") (pintype "passive"))
    )
    (net (code "26") (name "Net-(IC7-2-EN1)") (class "Default")
      (node (ref "IC7") (pin "2") (pinfunction "2-EN1_2") (pintype "bidirectional"))
      (node (ref "R28") (pin "1") (pinfunction "1_1") (pintype "passive"))
    )
    (net (code "27") (name "Net-(IC7-4-SW1)") (class "Default")
      (node (ref "IC7") (pin "4") (pinfunction "4-SW1_4") (pintype "bidirectional"))
      (node (ref "L5") (pin "1") (pinfunction "1_1") (pintype "passive"))
    )
    (net (code "28") (name "Net-(IC7-6-MODE{slash}SYNC)") (class "Default")
      (node (ref "IC7") (pin "6") (pinfunction "6-MODE/SYNC_6") (pintype "bidirectional"))
      (node (ref "R29") (pin "2") (pinfunction "2_2") (pintype "passive"))
      (node (ref "R30") (pin "1") (pinfunction "1_1") (pintype "passive"))
    )
    (net (code "29") (name "Net-(IC7-7-SW2)") (class "Default")
      (node (ref "IC7") (pin "7") (pinfunction "7-SW2_7") (pintype "bidirectional"))
      (node (ref "L4") (pin "1") (pinfunction "1_1") (pintype "passive"))
    )
    (net (code "30") (name "Net-(IC7-10-FB2)") (class "Default")
      (node (ref "C24") (pin "2") (pinfunction "2_2") (pintype "passive"))
      (node (ref "IC7") (pin "10") (pinfunction "10-FB2_10") (pintype "bidirectional"))
      (node (ref "R26") (pin "2") (pinfunction "2_2") (pintype "passive"))
      (node (ref "R27") (pin "1") (pinfunction "1_1") (pintype "passive"))
    )
    (net (code "31") (name "Net-(IC7-POR)") (class "Default")
      (node (ref "IC7") (pin "8") (pinfunction "POR_8") (pintype "bidirectional"))
      (node (ref "R36") (pin "2") (pinfunction "2_2") (pintype "passive"))
    )
    (net (code "32") (name "Net-(IC8-6-VDDANA)") (class "Default")
      (node (ref "C6") (pin "1") (pinfunction "1_1") (pintype "passive"))
      (node (ref "C7") (pin "1") (pinfunction "1_1") (pintype "passive"))
      (node (ref "IC8") (pin "6") (pinfunction "6-VDDANA_6") (pintype "bidirectional"))
      (node (ref "L1") (pin "2") (pinfunction "2_2") (pintype "passive"))
    )
    (net (code "33") (name "Net-(IC8-41-VDDCORE)") (class "Default")
      (node (ref "C10") (pin "1") (pinfunction "1_1") (pintype "passive"))
      (node (ref "C11") (pin "1") (pinfunction "1_1") (pintype "passive"))
      (node (ref "IC8") (pin "41") (pinfunction "41-VDDCORE_41") (pintype "bidirectional"))
      (node (ref "L2") (pin "1") (pinfunction "1_1") (pintype "passive"))
    )
    (net (code "34") (name "Net-(IC8-43-VSW)") (class "Default")
      (node (ref "IC8") (pin "43") (pinfunction "43-VSW_43") (pintype "bidirectional"))
      (node (ref "L2") (pin "2") (pinfunction "2_2") (pintype "passive"))
    )
    (net (code "35") (name "Net-(JP1-Pad1)") (class "Default")
      (node (ref "JP1") (pin "1") (pinfunction "1_1") (pintype "bidirectional"))
      (node (ref "JP2") (pin "2") (pinfunction "2_2") (pintype "bidirectional"))
    )
    (net (code "36") (name "Net-(JP4-Pad1)") (class "Default")
      (node (ref "JP4") (pin "1") (pinfunction "1_1") (pintype "passive"))
      (node (ref "R19") (pin "2") (pinfunction "2_2") (pintype "passive"))
    )
    (net (code "37") (name "Net-(LED1-PadA)") (class "Default")
      (node (ref "LED1") (pin "A") (pinfunction "A_A") (pintype "bidirectional"))
      (node (ref "R32") (pin "1") (pinfunction "1_1") (pintype "passive"))
    )
    (net (code "38") (name "Net-(LED2-PadA)") (class "Default")
      (node (ref "LED2") (pin "A") (pinfunction "A_A") (pintype "bidirectional"))
      (node (ref "R34") (pin "2") (pinfunction "2_2") (pintype "passive"))
    )
    (net (code "39") (name "Net-(Q1-D1)") (class "Default")
      (node (ref "LED1") (pin "K") (pinfunction "K_K") (pintype "bidirectional"))
      (node (ref "Q1") (pin "3") (pinfunction "D1_3") (pintype "bidirectional"))
    )
    (net (code "40") (name "Net-(Q1-D2)") (class "Default")
      (node (ref "LED2") (pin "K") (pinfunction "K_K") (pintype "bidirectional"))
      (node (ref "Q1") (pin "6") (pinfunction "D2_6") (pintype "bidirectional"))
    )
    (net (code "41") (name "Net-(R13-Pad2)") (class "Default")
      (node (ref "R13") (pin "2") (pinfunction "2_2") (pintype "passive"))
      (node (ref "USB1") (pin "P4") (pinfunction "P4_P4") (pintype "bidirectional"))
    )
    (net (code "42") (name "Net-(T1-D)") (class "Default")
      (node (ref "JP4") (pin "3") (pinfunction "3_3") (pintype "passive"))
      (node (ref "T1") (pin "3") (pinfunction "D_3") (pintype "passive"))
    )
    (net (code "43") (name "Net-(T1-G)") (class "Default")
      (node (ref "R20") (pin "1") (pinfunction "1_1") (pintype "passive"))
      (node (ref "T1") (pin "1") (pinfunction "G_1") (pintype "passive"))
    )
    (net (code "44") (name "P1V8") (class "Default")
      (node (ref "C24") (pin "1") (pinfunction "1_1") (pintype "passive"))
      (node (ref "C25") (pin "1") (pinfunction "1_1") (pintype "passive"))
      (node (ref "C28") (pin "1") (pinfunction "1_1") (pintype "passive"))
      (node (ref "IC2") (pin "11") (pinfunction "11-VDD_11") (pintype "bidirectional"))
      (node (ref "IC9") (pin "7") (pinfunction "7-VREF2_7") (pintype "bidirectional"))
      (node (ref "IC9") (pin "8") (pinfunction "8-EN_8") (pintype "bidirectional"))
      (node (ref "L4") (pin "2") (pinfunction "2_2") (pintype "passive"))
      (node (ref "R27") (pin "2") (pinfunction "2_2") (pintype "passive"))
      (node (ref "TP2") (pin "TP") (pinfunction "TP_TP") (pintype "input"))
    )
    (net (code "45") (name "P1V8-EN") (class "Default")
      (node (ref "IC7") (pin "9") (pinfunction "9-EN2_9") (pintype "bidirectional"))
      (node (ref "IC8") (pin "11") (pinfunction "11-PA06_11") (pintype "bidirectional"))
    )
    (net (code "46") (name "P3V3") (class "Default")
      (node (ref "C16") (pin "1") (pinfunction "1_1") (pintype "passive"))
      (node (ref "C2") (pin "1") (pinfunction "1_1") (pintype "passive"))
      (node (ref "C21") (pin "1") (pinfunction "1_1") (pintype "passive"))
      (node (ref "C23") (pin "1") (pinfunction "1_1") (pintype "passive"))
      (node (ref "C26") (pin "1") (pinfunction "1_1") (pintype "passive"))
      (node (ref "C27") (pin "1") (pinfunction "1_1") (pintype "passive"))
      (node (ref "C4") (pin "1") (pinfunction "1_1") (pintype "passive"))
      (node (ref "C5") (pin "1") (pinfunction "1_1") (pintype "passive"))
      (node (ref "C8") (pin "1") (pinfunction "1_1") (pintype "passive"))
      (node (ref "CON1") (pin "1") (pinfunction "1_1") (pintype "bidirectional"))
      (node (ref "IC1") (pin "1") (pinfunction "VIN_1") (pintype "bidirectional"))
      (node (ref "IC2") (pin "10") (pinfunction "9-VLED+_10") (pintype "bidirectional"))
      (node (ref "IC2") (pin "9") (pinfunction "9-VLED+_9") (pintype "bidirectional"))
      (node (ref "IC3") (pin "9") (pinfunction "9-VCC_9") (pintype "bidirectional"))
      (node (ref "IC5") (pin "8") (pinfunction "8-VCC_8") (pintype "bidirectional"))
      (node (ref "IC8") (pin "17") (pinfunction "17-VDDIO_17") (pintype "bidirectional"))
      (node (ref "IC8") (pin "36") (pinfunction "36-VDDIO_36") (pintype "bidirectional"))
      (node (ref "IC8") (pin "44") (pinfunction "44-VDDIN_44") (pintype "bidirectional"))
      (node (ref "IC9") (pin "2") (pinfunction "2-VREF1_2") (pintype "bidirectional"))
      (node (ref "L1") (pin "1") (pinfunction "1_1") (pintype "passive"))
      (node (ref "L5") (pin "2") (pinfunction "2_2") (pintype "passive"))
      (node (ref "R14") (pin "1") (pinfunction "1_1") (pintype "passive"))
      (node (ref "R17") (pin "2") (pinfunction "2_2") (pintype "passive"))
      (node (ref "R18") (pin "2") (pinfunction "2_2") (pintype "passive"))
      (node (ref "R22") (pin "2") (pinfunction "2_2") (pintype "passive"))
      (node (ref "R23") (pin "2") (pinfunction "2_2") (pintype "passive"))
      (node (ref "R25") (pin "2") (pinfunction "2_2") (pintype "passive"))
      (node (ref "R3") (pin "2") (pinfunction "2_2") (pintype "passive"))
      (node (ref "R31") (pin "2") (pinfunction "2_2") (pintype "passive"))
      (node (ref "R32") (pin "2") (pinfunction "2_2") (pintype "passive"))
      (node (ref "R33") (pin "2") (pinfunction "2_2") (pintype "passive"))
      (node (ref "R34") (pin "1") (pinfunction "1_1") (pintype "passive"))
      (node (ref "R6") (pin "2") (pinfunction "2_2") (pintype "passive"))
      (node (ref "R7") (pin "2") (pinfunction "2_2") (pintype "passive"))
    )
    (net (code "47") (name "P5V0") (class "Default")
      (node (ref "IC4") (pin "4") (pinfunction "VCC_4") (pintype "bidirectional"))
      (node (ref "R10") (pin "2") (pinfunction "2_2") (pintype "passive"))
      (node (ref "R12") (pin "1") (pinfunction "1_1") (pintype "passive"))
      (node (ref "USB1") (pin "P1") (pinfunction "P1_P1") (pintype "bidirectional"))
    )
    (net (code "48") (name "P5V0-UP") (class "Default")
      (node (ref "C18") (pin "1") (pinfunction "1_1") (pintype "passive"))
      (node (ref "D1") (pin "K") (pinfunction "C_K") (pintype "passive"))
      (node (ref "JP4") (pin "6") (pinfunction "6_6") (pintype "passive"))
      (node (ref "JP5") (pin "2") (pinfunction "2_2") (pintype "bidirectional"))
      (node (ref "R15") (pin "2") (pinfunction "2_2") (pintype "passive"))
      (node (ref "R19") (pin "1") (pinfunction "1_1") (pintype "passive"))
    )
    (net (code "49") (name "RESET") (class "Default")
      (node (ref "IC8") (pin "40") (pinfunction "40-RESET_40") (pintype "bidirectional"))
      (node (ref "R8") (pin "2") (pinfunction "2_2") (pintype "passive"))
    )
    (net (code "50") (name "RST") (class "Default")
      (node (ref "C14") (pin "1") (pinfunction "1_1") (pintype "passive"))
      (node (ref "CON1") (pin "4") (pinfunction "4_4") (pintype "bidirectional"))
      (node (ref "R23") (pin "1") (pinfunction "1_1") (pintype "passive"))
      (node (ref "R8") (pin "1") (pinfunction "1_1") (pintype "passive"))
      (node (ref "RESET") (pin "1") (pinfunction "1_1") (pintype "bidirectional"))
      (node (ref "RESET") (pin "3") (pinfunction "2_3") (pintype "bidirectional"))
    )
    (net (code "51") (name "SCL") (class "Default")
      (node (ref "CON1") (pin "6") (pinfunction "6_6") (pintype "bidirectional"))
      (node (ref "IC3") (pin "3") (pinfunction "3-SCL_3") (pintype "bidirectional"))
      (node (ref "IC5") (pin "2") (pinfunction "2-SCL_2") (pintype "bidirectional"))
      (node (ref "IC8") (pin "14") (pinfunction "14-PA09_14") (pintype "bidirectional"))
      (node (ref "IC9") (pin "3") (pinfunction "3-SCL1_3") (pintype "bidirectional"))
      (node (ref "JP3") (pin "10") (pinfunction "10_10") (pintype "bidirectional"))
      (node (ref "R18") (pin "1") (pinfunction "1_1") (pintype "passive"))
    )
    (net (code "52") (name "SCL-1V8") (class "Default")
      (node (ref "IC2") (pin "2") (pinfunction "2-SCL_2") (pintype "bidirectional"))
      (node (ref "IC9") (pin "6") (pinfunction "6-SCL2_6") (pintype "bidirectional"))
    )
    (net (code "53") (name "SDA") (class "Default")
      (node (ref "CON1") (pin "5") (pinfunction "5_5") (pintype "bidirectional"))
      (node (ref "IC3") (pin "2") (pinfunction "2-SDA_2") (pintype "bidirectional"))
      (node (ref "IC5") (pin "1") (pinfunction "1-SDA_1") (pintype "bidirectional"))
      (node (ref "IC8") (pin "13") (pinfunction "13-PA08_13") (pintype "bidirectional"))
      (node (ref "IC9") (pin "4") (pinfunction "4-SDA1_4") (pintype "bidirectional"))
      (node (ref "JP3") (pin "8") (pinfunction "8_8") (pintype "bidirectional"))
      (node (ref "R17") (pin "1") (pinfunction "1_1") (pintype "passive"))
    )
    (net (code "54") (name "SDA-1V8") (class "Default")
      (node (ref "IC2") (pin "3") (pinfunction "3-SDA_3") (pintype "bidirectional"))
      (node (ref "IC9") (pin "5") (pinfunction "5-SDA2_5") (pintype "bidirectional"))
    )
    (net (code "55") (name "SENS-EN") (class "Default")
      (node (ref "IC8") (pin "3") (pinfunction "3-PA02_3") (pintype "bidirectional"))
      (node (ref "R20") (pin "2") (pinfunction "2_2") (pintype "passive"))
    )
    (net (code "56") (name "SERVICE") (class "Default")
      (node (ref "C9") (pin "1") (pinfunction "1_1") (pintype "passive"))
      (node (ref "IC8") (pin "31") (pinfunction "31-PA22_31") (pintype "bidirectional"))
      (node (ref "R33") (pin "1") (pinfunction "1_1") (pintype "passive"))
      (node (ref "SERVICE") (pin "1") (pinfunction "1_1") (pintype "bidirectional"))
      (node (ref "SERVICE") (pin "3") (pinfunction "2_3") (pintype "bidirectional"))
    )
    (net (code "57") (name "STC-ALARM") (class "Default")
      (node (ref "IC3") (pin "1") (pinfunction "1-ALM_1") (pintype "bidirectional"))
      (node (ref "IC8") (pin "15") (pinfunction "15-PA10_15") (pintype "bidirectional"))
      (node (ref "R6") (pin "1") (pinfunction "1_1") (pintype "passive"))
    )
    (net (code "58") (name "STC-CG") (class "Default")
      (node (ref "IC3") (pin "6") (pinfunction "6-CG_6") (pintype "bidirectional"))
      (node (ref "JP1") (pin "3") (pinfunction "3_3") (pintype "bidirectional"))
      (node (ref "R1") (pin "1") (pinfunction "1_1") (pintype "passive"))
    )
    (net (code "59") (name "STC-RSTIO") (class "Default")
      (node (ref "IC3") (pin "7") (pinfunction "7-RSTIO_7") (pintype "bidirectional"))
      (node (ref "IC8") (pin "12") (pinfunction "12-PA07_12") (pintype "bidirectional"))
      (node (ref "R7") (pin "1") (pinfunction "1_1") (pintype "passive"))
    )
    (net (code "60") (name "SWDCLK") (class "Default")
      (node (ref "CON1") (pin "3") (pinfunction "3_3") (pintype "bidirectional"))
      (node (ref "IC8") (pin "45") (pinfunction "45-PA30_45") (pintype "bidirectional"))
    )
    (net (code "61") (name "SWDIO") (class "Default")
      (node (ref "CON1") (pin "2") (pinfunction "2_2") (pintype "bidirectional"))
      (node (ref "IC8") (pin "46") (pinfunction "46-PA31_46") (pintype "bidirectional"))
    )
    (net (code "62") (name "TEMP-ALERT") (class "Default")
      (node (ref "IC5") (pin "3") (pinfunction "3-ALERT_3") (pintype "bidirectional"))
      (node (ref "IC8") (pin "10") (pinfunction "10-PA05_10") (pintype "bidirectional"))
      (node (ref "R22") (pin "1") (pinfunction "1_1") (pintype "passive"))
    )
    (net (code "63") (name "USB-DETECT") (class "Default")
      (node (ref "IC8") (pin "16") (pinfunction "16-PA11_16") (pintype "bidirectional"))
      (node (ref "R10") (pin "1") (pinfunction "1_1") (pintype "passive"))
      (node (ref "R11") (pin "2") (pinfunction "2_2") (pintype "passive"))
    )
    (net (code "64") (name "USB_N") (class "Default")
      (node (ref "IC4") (pin "3") (pinfunction "IO2_3") (pintype "bidirectional"))
      (node (ref "IC8") (pin "33") (pinfunction "33-PA24_33") (pintype "bidirectional"))
      (node (ref "USB1") (pin "P2") (pinfunction "P2_P2") (pintype "bidirectional"))
    )
    (net (code "65") (name "USB_P") (class "Default")
      (node (ref "IC4") (pin "2") (pinfunction "IO1_2") (pintype "bidirectional"))
      (node (ref "IC8") (pin "34") (pinfunction "34-PA25_34") (pintype "bidirectional"))
      (node (ref "USB1") (pin "P3") (pinfunction "P3_P3") (pintype "bidirectional"))
    )
    (net (code "66") (name "VBAT") (class "Default")
      (node (ref "C1") (pin "1") (pinfunction "1_1") (pintype "passive"))
      (node (ref "C17") (pin "1") (pinfunction "1_1") (pintype "passive"))
      (node (ref "IC6") (pin "6") (pinfunction "6-VIN_6") (pintype "bidirectional"))
      (node (ref "IC7") (pin "3") (pinfunction "3-VIN_3") (pintype "bidirectional"))
      (node (ref "JP2") (pin "1") (pinfunction "1_1") (pintype "bidirectional"))
      (node (ref "L3") (pin "1") (pinfunction "1_1") (pintype "passive"))
      (node (ref "R12") (pin "2") (pinfunction "2_2") (pintype "passive"))
      (node (ref "R28") (pin "2") (pinfunction "2_2") (pintype "passive"))
      (node (ref "R29") (pin "1") (pinfunction "1_1") (pintype "passive"))
      (node (ref "R5") (pin "1") (pinfunction "1_1") (pintype "passive"))
      (node (ref "TP1") (pin "TP") (pinfunction "TP_TP") (pintype "input"))
    )
    (net (code "67") (name "XIN") (class "Default")
      (node (ref "C12") (pin "1") (pinfunction "1_1") (pintype "passive"))
      (node (ref "IC8") (pin "23") (pinfunction "23-PA14-XIN_23") (pintype "bidirectional"))
      (node (ref "OSC1") (pin "1") (pinfunction "P$1_1") (pintype "bidirectional"))
    )
    (net (code "68") (name "XIN32") (class "Default")
      (node (ref "C19") (pin "1") (pinfunction "1_1") (pintype "passive"))
      (node (ref "IC8") (pin "1") (pinfunction "1-PA00-XIN32_1") (pintype "bidirectional"))
      (node (ref "OSC2") (pin "2") (pinfunction "P$2_2") (pintype "bidirectional"))
    )
    (net (code "69") (name "XOUT") (class "Default")
      (node (ref "C13") (pin "1") (pinfunction "1_1") (pintype "passive"))
      (node (ref "IC8") (pin "24") (pinfunction "24-PA15-XOUT_24") (pintype "bidirectional"))
      (node (ref "OSC1") (pin "3") (pinfunction "P$2_3") (pintype "bidirectional"))
    )
    (net (code "70") (name "XOUT32") (class "Default")
      (node (ref "C20") (pin "1") (pinfunction "1_1") (pintype "passive"))
      (node (ref "IC8") (pin "2") (pinfunction "2-PA01-XOUT32_2") (pintype "bidirectional"))
      (node (ref "OSC2") (pin "1") (pinfunction "P$1_1") (pintype "bidirectional"))
    )
    (net (code "71") (name "unconnected-(IC2-5-R-DRV-Pad5)") (class "Default")
      (node (ref "IC2") (pin "5") (pinfunction "5-R-DRV_5") (pintype "bidirectional"))
    )
    (net (code "72") (name "unconnected-(IC2-6-IR-DRV-Pad6)") (class "Default")
      (node (ref "IC2") (pin "6") (pinfunction "6-IR-DRV_6") (pintype "bidirectional"))
    )
    (net (code "73") (name "unconnected-(IC2-7-G-DRV-Pad7)") (class "Default")
      (node (ref "IC2") (pin "7") (pinfunction "7-G-DRV_7") (pintype "bidirectional"))
    )
    (net (code "74") (name "unconnected-(IC3-4-NC-Pad4)") (class "Default")
      (node (ref "IC3") (pin "4") (pinfunction "4-NC_4") (pintype "bidirectional"))
    )
    (net (code "75") (name "unconnected-(IC8-4-PA03-Pad4)") (class "Default")
      (node (ref "IC8") (pin "4") (pinfunction "4-PA03_4") (pintype "bidirectional"))
    )
    (net (code "76") (name "unconnected-(IC8-9-PA04-Pad9)") (class "Default")
      (node (ref "IC8") (pin "9") (pinfunction "9-PA04_9") (pintype "bidirectional"))
    )
    (net (code "77") (name "unconnected-(IC8-32-PA23-Pad32)") (class "Default")
      (node (ref "IC8") (pin "32") (pinfunction "32-PA23_32") (pintype "bidirectional"))
    )
    (net (code "78") (name "unconnected-(IC8-47-PB02-Pad47)") (class "Default")
      (node (ref "IC8") (pin "47") (pinfunction "47-PB02_47") (pintype "bidirectional"))
    )
    (net (code "79") (name "unconnected-(IC8-48-PB03-Pad48)") (class "Default")
      (node (ref "IC8") (pin "48") (pinfunction "48-PB03_48") (pintype "bidirectional"))
    )
    (net (code "80") (name "unconnected-(JP3-Pad21)") (class "Default")
      (node (ref "JP3") (pin "21") (pinfunction "21_21") (pintype "bidirectional"))
    )
    (net (code "81") (name "unconnected-(JP3-Pad23)") (class "Default")
      (node (ref "JP3") (pin "23") (pinfunction "23_23") (pintype "bidirectional"))
    )
    (net (code "82") (name "unconnected-(JP3-Pad25)") (class "Default")
      (node (ref "JP3") (pin "25") (pinfunction "25_25") (pintype "bidirectional"))
    )
    (net (code "83") (name "unconnected-(JP3-Pad27)") (class "Default")
      (node (ref "JP3") (pin "27") (pinfunction "27_27") (pintype "bidirectional"))
    )
    (net (code "84") (name "unconnected-(JP3-Pad29)") (class "Default")
      (node (ref "JP3") (pin "29") (pinfunction "29_29") (pintype "bidirectional"))
    )
    (net (code "85") (name "unconnected-(JP3-Pad31)") (class "Default")
      (node (ref "JP3") (pin "31") (pinfunction "31_31") (pintype "bidirectional"))
    )
    (net (code "86") (name "unconnected-(JP3-Pad33)") (class "Default")
      (node (ref "JP3") (pin "33") (pinfunction "33_33") (pintype "bidirectional"))
    )
    (net (code "87") (name "unconnected-(JP3-Pad35)") (class "Default")
      (node (ref "JP3") (pin "35") (pinfunction "35_35") (pintype "bidirectional"))
    )
    (net (code "88") (name "unconnected-(JP3-Pad36)") (class "Default")
      (node (ref "JP3") (pin "36") (pinfunction "36_36") (pintype "bidirectional"))
    )
    (net (code "89") (name "unconnected-(JP3-Pad37)") (class "Default")
      (node (ref "JP3") (pin "37") (pinfunction "37_37") (pintype "bidirectional"))
    )
    (net (code "90") (name "unconnected-(JP3-Pad38)") (class "Default")
      (node (ref "JP3") (pin "38") (pinfunction "38_38") (pintype "bidirectional"))
    )
    (net (code "91") (name "unconnected-(JP3-Pad39)") (class "Default")
      (node (ref "JP3") (pin "39") (pinfunction "39_39") (pintype "bidirectional"))
    )
    (net (code "92") (name "unconnected-(JP3-Pad40)") (class "Default")
      (node (ref "JP3") (pin "40") (pinfunction "40_40") (pintype "bidirectional"))
    )
    (net (code "93") (name "unconnected-(JP3-Pad41)") (class "Default")
      (node (ref "JP3") (pin "41") (pinfunction "41_41") (pintype "bidirectional"))
    )
    (net (code "94") (name "unconnected-(JP3-Pad42)") (class "Default")
      (node (ref "JP3") (pin "42") (pinfunction "42_42") (pintype "bidirectional"))
    )
    (net (code "95") (name "unconnected-(JP3-Pad43)") (class "Default")
      (node (ref "JP3") (pin "43") (pinfunction "43_43") (pintype "bidirectional"))
    )
    (net (code "96") (name "unconnected-(JP3-Pad44)") (class "Default")
      (node (ref "JP3") (pin "44") (pinfunction "44_44") (pintype "bidirectional"))
    )
    (net (code "97") (name "unconnected-(JP3-Pad45)") (class "Default")
      (node (ref "JP3") (pin "45") (pinfunction "45_45") (pintype "bidirectional"))
    )
    (net (code "98") (name "unconnected-(JP3-Pad46)") (class "Default")
      (node (ref "JP3") (pin "46") (pinfunction "46_46") (pintype "bidirectional"))
    )
    (net (code "99") (name "unconnected-(JP3-Pad47)") (class "Default")
      (node (ref "JP3") (pin "47") (pinfunction "47_47") (pintype "bidirectional"))
    )
    (net (code "100") (name "unconnected-(JP3-Pad48)") (class "Default")
      (node (ref "JP3") (pin "48") (pinfunction "48_48") (pintype "bidirectional"))
    )
    (net (code "101") (name "unconnected-(JP3-Pad49)") (class "Default")
      (node (ref "JP3") (pin "49") (pinfunction "49_49") (pintype "bidirectional"))
    )
    (net (code "102") (name "unconnected-(JP3-Pad50)") (class "Default")
      (node (ref "JP3") (pin "50") (pinfunction "50_50") (pintype "bidirectional"))
    )
    (net (code "103") (name "unconnected-(JP3-Pad51)") (class "Default")
      (node (ref "JP3") (pin "51") (pinfunction "51_51") (pintype "bidirectional"))
    )
    (net (code "104") (name "unconnected-(JP3-Pad52)") (class "Default")
      (node (ref "JP3") (pin "52") (pinfunction "52_52") (pintype "bidirectional"))
    )
    (net (code "105") (name "unconnected-(JP3-Pad53)") (class "Default")
      (node (ref "JP3") (pin "53") (pinfunction "53_53") (pintype "bidirectional"))
    )
    (net (code "106") (name "unconnected-(JP3-Pad54)") (class "Default")
      (node (ref "JP3") (pin "54") (pinfunction "54_54") (pintype "bidirectional"))
    )
    (net (code "107") (name "unconnected-(JP3-Pad55)") (class "Default")
      (node (ref "JP3") (pin "55") (pinfunction "55_55") (pintype "bidirectional"))
    )
    (net (code "108") (name "unconnected-(JP3-Pad56)") (class "Default")
      (node (ref "JP3") (pin "56") (pinfunction "56_56") (pintype "bidirectional"))
    )
    (net (code "109") (name "unconnected-(JP3-Pad57)") (class "Default")
      (node (ref "JP3") (pin "57") (pinfunction "57_57") (pintype "bidirectional"))
    )
    (net (code "110") (name "unconnected-(JP3-Pad58)") (class "Default")
      (node (ref "JP3") (pin "58") (pinfunction "58_58") (pintype "bidirectional"))
    )
    (net (code "111") (name "unconnected-(JP3-Pad59)") (class "Default")
      (node (ref "JP3") (pin "59") (pinfunction "59_59") (pintype "bidirectional"))
    )
    (net (code "112") (name "unconnected-(JP3-Pad60)") (class "Default")
      (node (ref "JP3") (pin "60") (pinfunction "60_60") (pintype "bidirectional"))
    )
    (net (code "113") (name "unconnected-(JP3-Pad61)") (class "Default")
      (node (ref "JP3") (pin "61") (pinfunction "61_61") (pintype "bidirectional"))
    )
    (net (code "114") (name "unconnected-(JP3-Pad62)") (class "Default")
      (node (ref "JP3") (pin "62") (pinfunction "62_62") (pintype "bidirectional"))
    )
    (net (code "115") (name "unconnected-(JP3-Pad63)") (class "Default")
      (node (ref "JP3") (pin "63") (pinfunction "63_63") (pintype "bidirectional"))
    )
    (net (code "116") (name "unconnected-(JP3-Pad64)") (class "Default")
      (node (ref "JP3") (pin "64") (pinfunction "64_64") (pintype "bidirectional"))
    )
    (net (code "117") (name "unconnected-(JP3-Pad65)") (class "Default")
      (node (ref "JP3") (pin "65") (pinfunction "65_65") (pintype "bidirectional"))
    )
    (net (code "118") (name "unconnected-(JP3-Pad66)") (class "Default")
      (node (ref "JP3") (pin "66") (pinfunction "66_66") (pintype "bidirectional"))
    )
    (net (code "119") (name "unconnected-(JP3-Pad67)") (class "Default")
      (node (ref "JP3") (pin "67") (pinfunction "67_67") (pintype "bidirectional"))
    )
    (net (code "120") (name "unconnected-(JP3-Pad68)") (class "Default")
      (node (ref "JP3") (pin "68") (pinfunction "68_68") (pintype "bidirectional"))
    )
    (net (code "121") (name "unconnected-(JP3-Pad69)") (class "Default")
      (node (ref "JP3") (pin "69") (pinfunction "69_69") (pintype "bidirectional"))
    )
    (net (code "122") (name "unconnected-(JP3-Pad70)") (class "Default")
      (node (ref "JP3") (pin "70") (pinfunction "70_70") (pintype "bidirectional"))
    )
    (net (code "123") (name "unconnected-(JP3-Pad71)") (class "Default")
      (node (ref "JP3") (pin "71") (pinfunction "71_71") (pintype "bidirectional"))
    )
    (net (code "124") (name "unconnected-(JP3-Pad72)") (class "Default")
      (node (ref "JP3") (pin "72") (pinfunction "72_72") (pintype "bidirectional"))
    )
    (net (code "125") (name "unconnected-(JP3-Pad73)") (class "Default")
      (node (ref "JP3") (pin "73") (pinfunction "73_73") (pintype "bidirectional"))
    )
    (net (code "126") (name "unconnected-(JP3-Pad74)") (class "Default")
      (node (ref "JP3") (pin "74") (pinfunction "74_74") (pintype "bidirectional"))
    )
    (net (code "127") (name "unconnected-(JP3-Pad75)") (class "Default")
      (node (ref "JP3") (pin "75") (pinfunction "75_75") (pintype "bidirectional"))
    )
  )
)
